# IV_Swinger_2_cell.net
KiCad netlist of a schematic drawn in EAGLE
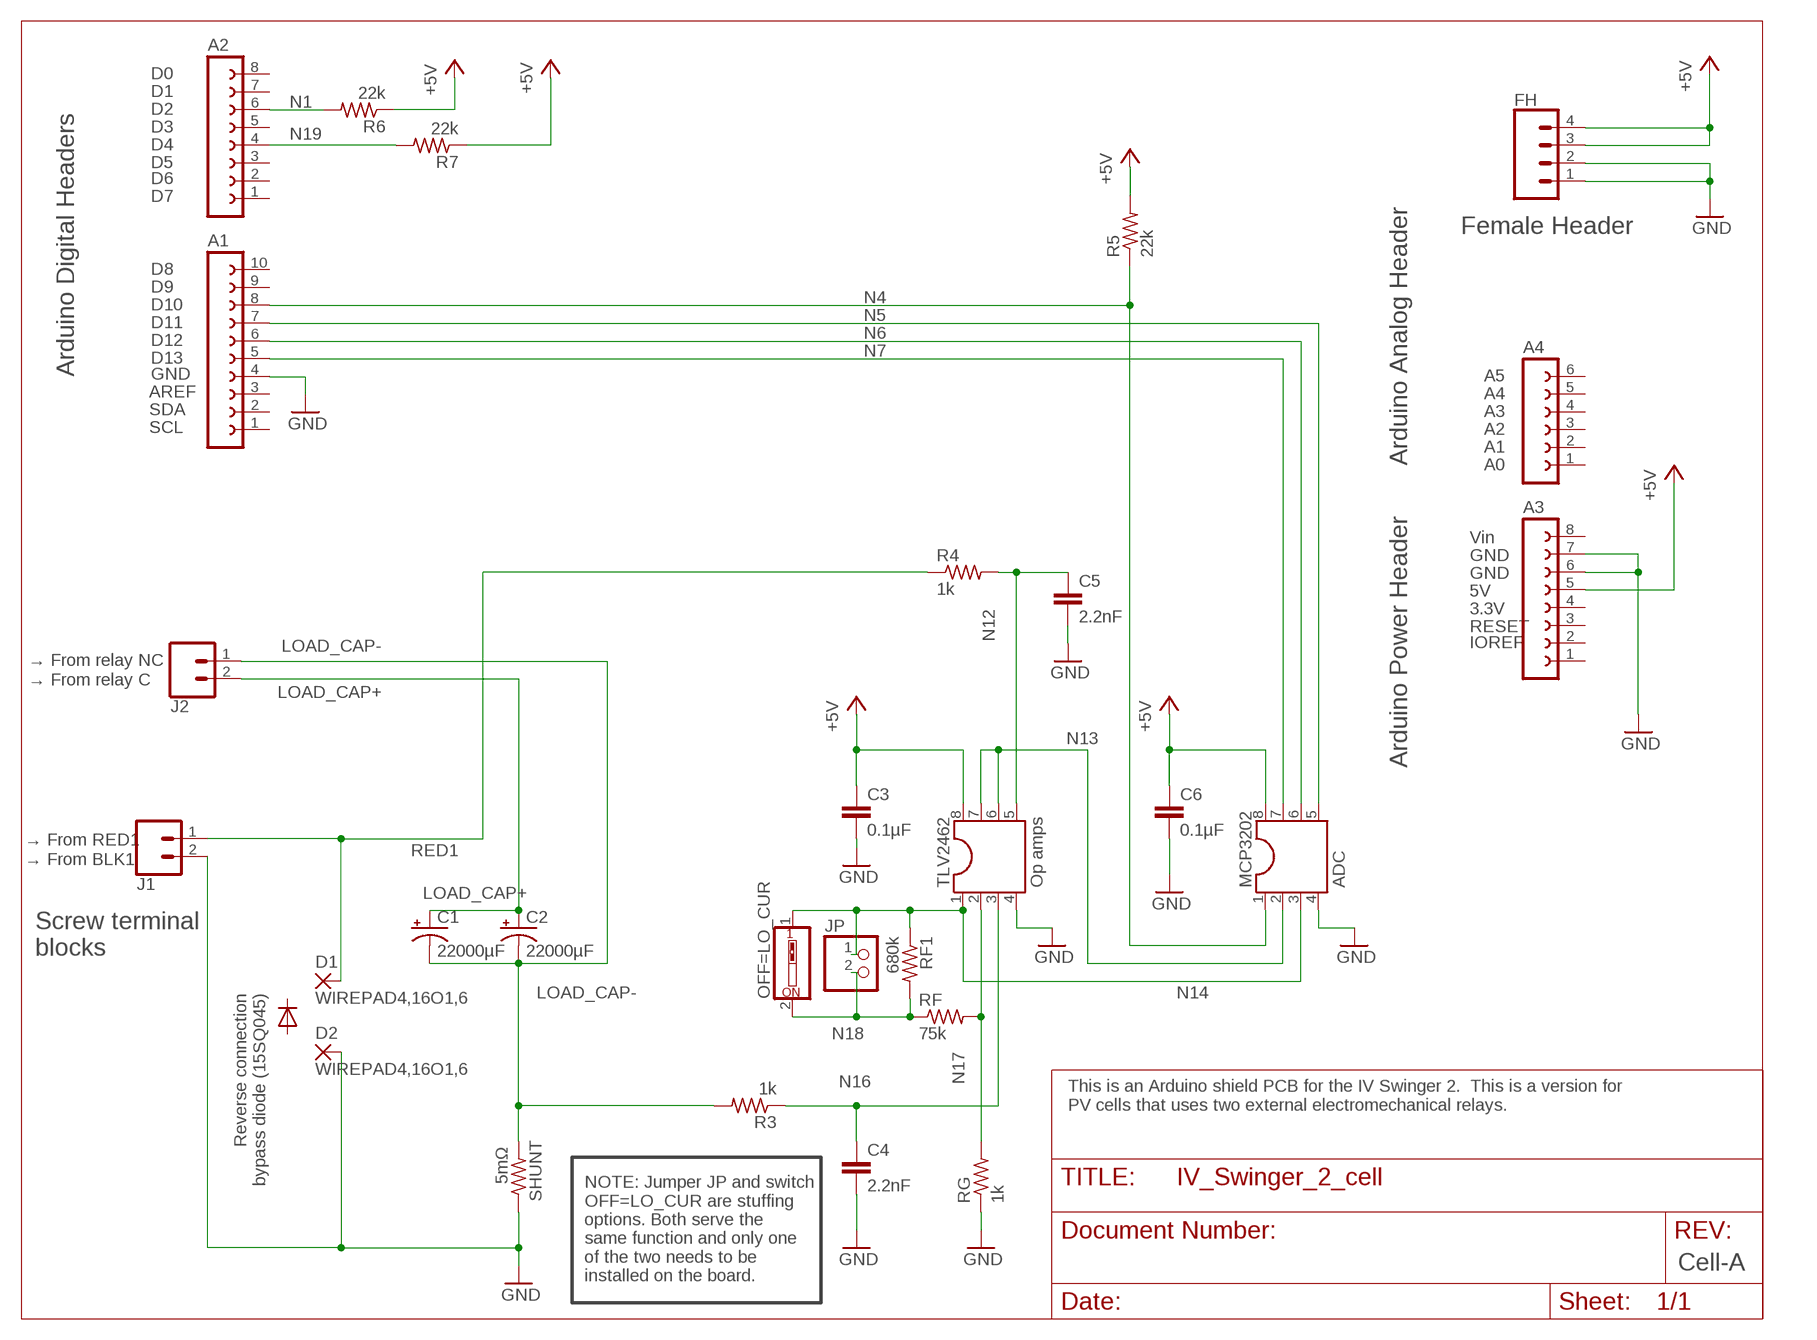
[diagram p0: schematic, sheet 1]

(export (version "E")
  (design (tool "Eeschema 10.0.6"))
  (components
    (comp (ref "A1")
      (value "FE10-1")
      (footprint "eagle-import:FE10")
      (libsource (lib "eagle-import") (part "FE10-1"))
    )
    (comp (ref "A2")
      (value "FE08-1")
      (footprint "eagle-import:FE08")
      (libsource (lib "eagle-import") (part "FE08-1"))
    )
    (comp (ref "A3")
      (value "FE08-1")
      (footprint "eagle-import:FE08")
      (libsource (lib "eagle-import") (part "FE08-1"))
    )
    (comp (ref "A4")
      (value "FE06-1")
      (footprint "eagle-import:FE06")
      (libsource (lib "eagle-import") (part "FE06-1"))
    )
    (comp (ref "C1")
      (value "22000µF")
      (footprint "eagle-import:E7,5-18")
      (libsource (lib "eagle-import") (part "CPOL-USE7.5-18"))
    )
    (comp (ref "C2")
      (value "22000µF")
      (footprint "eagle-import:E7,5-18")
      (libsource (lib "eagle-import") (part "CPOL-USE7.5-18"))
    )
    (comp (ref "C3")
      (value "0.1µF")
      (footprint "eagle-import:C025-030X050")
      (libsource (lib "eagle-import") (part "C-EU025-030X050"))
    )
    (comp (ref "C4")
      (value "2.2nF")
      (footprint "eagle-import:C025-030X050")
      (libsource (lib "eagle-import") (part "C-EU025-030X050"))
    )
    (comp (ref "C5")
      (value "2.2nF")
      (footprint "eagle-import:C025-030X050")
      (libsource (lib "eagle-import") (part "C-EU025-030X050"))
    )
    (comp (ref "C6")
      (value "0.1µF")
      (footprint "eagle-import:C025-030X050")
      (libsource (lib "eagle-import") (part "C-EU025-030X050"))
    )
    (comp (ref "D1")
      (value "WIREPAD4,16O1,6")
      (footprint "eagle-import:4,16O1,6")
      (fields (field (name "SPICEPREFIX") "X"))
      (libsource (lib "eagle-import") (part "WIREPAD4,16O1,6"))
    )
    (comp (ref "D2")
      (value "WIREPAD4,16O1,6")
      (footprint "eagle-import:4,16O1,6")
      (libsource (lib "eagle-import") (part "WIREPAD4,16O1,6"))
    )
    (comp (ref "FH")
      (value "CONN_04LONGPADS")
      (footprint "eagle-import:1X04_LONGPADS")
      (libsource (lib "eagle-import") (part "CONN_04LONGPADS"))
    )
    (comp (ref "J1")
      (value "CONN_025MM")
      (footprint "eagle-import:SCREWTERMINAL-5MM-2")
      (libsource (lib "eagle-import") (part "CONN_025MM"))
    )
    (comp (ref "J2")
      (value "CONN_025MM")
      (footprint "eagle-import:SCREWTERMINAL-5MM-2")
      (libsource (lib "eagle-import") (part "CONN_025MM"))
    )
    (comp (ref "JP")
      (value "PINHD-1X2")
      (footprint "eagle-import:1X02")
      (libsource (lib "eagle-import") (part "PINHD-1X2"))
    )
    (comp (ref "MCP3202")
      (value "ADC")
      (footprint "eagle-import:SOCKET-08")
      (libsource (lib "eagle-import") (part "DIL8S"))
    )
    (comp (ref "OFF=LO_CUR")
      (value "SW_DIP-1")
      (footprint "eagle-import:EDG-01")
      (libsource (lib "eagle-import") (part "SW_DIP-1"))
    )
    (comp (ref "R3")
      (value "1k")
      (footprint "eagle-import:0207_10")
      (libsource (lib "eagle-import") (part "R-US_0207/10"))
    )
    (comp (ref "R4")
      (value "1k")
      (footprint "eagle-import:0207_10")
      (libsource (lib "eagle-import") (part "R-US_0207/10"))
    )
    (comp (ref "R5")
      (value "22k")
      (footprint "eagle-import:0207_10")
      (libsource (lib "eagle-import") (part "R-US_0207/10"))
    )
    (comp (ref "R6")
      (value "22k")
      (footprint "eagle-import:0207_10")
      (libsource (lib "eagle-import") (part "R-US_0207/10"))
    )
    (comp (ref "R7")
      (value "22k")
      (footprint "eagle-import:0207_10")
      (libsource (lib "eagle-import") (part "R-US_0207/10"))
    )
    (comp (ref "RF")
      (value "75k")
      (footprint "eagle-import:0207_10")
      (libsource (lib "eagle-import") (part "R-US_0207/10"))
    )
    (comp (ref "RF1")
      (value "680k")
      (footprint "eagle-import:0207_10")
      (libsource (lib "eagle-import") (part "R-US_0207/10"))
    )
    (comp (ref "RG")
      (value "1k")
      (footprint "eagle-import:0207_10")
      (libsource (lib "eagle-import") (part "R-US_0207/10"))
    )
    (comp (ref "SHUNT")
      (value "5mΩ")
      (footprint "eagle-import:0617_17")
      (libsource (lib "eagle-import") (part "R-US_0617/17"))
    )
    (comp (ref "TLV2462")
      (value "Op amps")
      (footprint "eagle-import:SOCKET-08")
      (libsource (lib "eagle-import") (part "DIL8S"))
    )
  )
  (nets
    (net (code "1") (name "+5V") (class "Default")
      (node (ref "A3") (pin "5") (pinfunction "5_5") (pintype "passive"))
      (node (ref "C3") (pin "1") (pinfunction "1_1") (pintype "passive"))
      (node (ref "C6") (pin "1") (pinfunction "1_1") (pintype "passive"))
      (node (ref "FH") (pin "3") (pinfunction "3_3") (pintype "passive"))
      (node (ref "FH") (pin "4") (pinfunction "4_4") (pintype "passive"))
      (node (ref "MCP3202") (pin "8") (pinfunction "8_8") (pintype "passive"))
      (node (ref "R5") (pin "2") (pinfunction "2_2") (pintype "passive"))
      (node (ref "R6") (pin "1") (pinfunction "1_1") (pintype "passive"))
      (node (ref "R7") (pin "1") (pinfunction "1_1") (pintype "passive"))
      (node (ref "TLV2462") (pin "8") (pinfunction "8_8") (pintype "passive"))
    )
    (net (code "2") (name "/LOAD_CAP+") (class "Default")
      (node (ref "C1") (pin "+") (pinfunction "+_+") (pintype "passive"))
      (node (ref "C2") (pin "+") (pinfunction "+_+") (pintype "passive"))
      (node (ref "J2") (pin "2") (pinfunction "2_2") (pintype "passive"))
    )
    (net (code "3") (name "/LOAD_CAP-") (class "Default")
      (node (ref "C1") (pin "-") (pinfunction "-_-") (pintype "passive"))
      (node (ref "C2") (pin "-") (pinfunction "-_-") (pintype "passive"))
      (node (ref "J2") (pin "1") (pinfunction "1_1") (pintype "passive"))
      (node (ref "R3") (pin "2") (pinfunction "2_2") (pintype "passive"))
      (node (ref "SHUNT") (pin "2") (pinfunction "2_2") (pintype "passive"))
    )
    (net (code "4") (name "/N1") (class "Default")
      (node (ref "A2") (pin "6") (pinfunction "6_6") (pintype "passive"))
      (node (ref "R6") (pin "2") (pinfunction "2_2") (pintype "passive"))
    )
    (net (code "5") (name "/N4") (class "Default")
      (node (ref "A1") (pin "8") (pinfunction "8_8") (pintype "passive"))
      (node (ref "MCP3202") (pin "1") (pinfunction "1_1") (pintype "passive"))
      (node (ref "R5") (pin "1") (pinfunction "1_1") (pintype "passive"))
    )
    (net (code "6") (name "/N5") (class "Default")
      (node (ref "A1") (pin "7") (pinfunction "7_7") (pintype "passive"))
      (node (ref "MCP3202") (pin "5") (pinfunction "5_5") (pintype "passive"))
    )
    (net (code "7") (name "/N6") (class "Default")
      (node (ref "A1") (pin "6") (pinfunction "6_6") (pintype "passive"))
      (node (ref "MCP3202") (pin "6") (pinfunction "6_6") (pintype "passive"))
    )
    (net (code "8") (name "/N7") (class "Default")
      (node (ref "A1") (pin "5") (pinfunction "5_5") (pintype "passive"))
      (node (ref "MCP3202") (pin "7") (pinfunction "7_7") (pintype "passive"))
    )
    (net (code "9") (name "/N12") (class "Default")
      (node (ref "C5") (pin "1") (pinfunction "1_1") (pintype "passive"))
      (node (ref "R4") (pin "2") (pinfunction "2_2") (pintype "passive"))
      (node (ref "TLV2462") (pin "5") (pinfunction "5_5") (pintype "passive"))
    )
    (net (code "10") (name "/N13") (class "Default")
      (node (ref "MCP3202") (pin "2") (pinfunction "2_2") (pintype "passive"))
      (node (ref "TLV2462") (pin "6") (pinfunction "6_6") (pintype "passive"))
      (node (ref "TLV2462") (pin "7") (pinfunction "7_7") (pintype "passive"))
    )
    (net (code "11") (name "/N14") (class "Default")
      (node (ref "JP") (pin "1") (pinfunction "1_1") (pintype "passive"))
      (node (ref "MCP3202") (pin "3") (pinfunction "3_3") (pintype "passive"))
      (node (ref "OFF=LO_CUR") (pin "1") (pinfunction "1_1") (pintype "passive"))
      (node (ref "RF1") (pin "1") (pinfunction "1_1") (pintype "passive"))
      (node (ref "TLV2462") (pin "1") (pinfunction "1_1") (pintype "passive"))
    )
    (net (code "12") (name "/N16") (class "Default")
      (node (ref "C4") (pin "1") (pinfunction "1_1") (pintype "passive"))
      (node (ref "R3") (pin "1") (pinfunction "1_1") (pintype "passive"))
      (node (ref "TLV2462") (pin "3") (pinfunction "3_3") (pintype "passive"))
    )
    (net (code "13") (name "/N17") (class "Default")
      (node (ref "RF") (pin "2") (pinfunction "2_2") (pintype "passive"))
      (node (ref "RG") (pin "2") (pinfunction "2_2") (pintype "passive"))
      (node (ref "TLV2462") (pin "2") (pinfunction "2_2") (pintype "passive"))
    )
    (net (code "14") (name "/N18") (class "Default")
      (node (ref "JP") (pin "2") (pinfunction "2_2") (pintype "passive"))
      (node (ref "OFF=LO_CUR") (pin "2") (pinfunction "2_2") (pintype "passive"))
      (node (ref "RF") (pin "1") (pinfunction "1_1") (pintype "passive"))
      (node (ref "RF1") (pin "2") (pinfunction "2_2") (pintype "passive"))
    )
    (net (code "15") (name "/N19") (class "Default")
      (node (ref "A2") (pin "4") (pinfunction "4_4") (pintype "passive"))
      (node (ref "R7") (pin "2") (pinfunction "2_2") (pintype "passive"))
    )
    (net (code "16") (name "/RED1") (class "Default")
      (node (ref "D1") (pin "1") (pinfunction "P_1") (pintype "passive"))
      (node (ref "J1") (pin "1") (pinfunction "1_1") (pintype "passive"))
      (node (ref "R4") (pin "1") (pinfunction "1_1") (pintype "passive"))
    )
    (net (code "17") (name "GND") (class "Default")
      (node (ref "A1") (pin "4") (pinfunction "4_4") (pintype "passive"))
      (node (ref "A3") (pin "6") (pinfunction "6_6") (pintype "passive"))
      (node (ref "A3") (pin "7") (pinfunction "7_7") (pintype "passive"))
      (node (ref "C3") (pin "2") (pinfunction "2_2") (pintype "passive"))
      (node (ref "C4") (pin "2") (pinfunction "2_2") (pintype "passive"))
      (node (ref "C5") (pin "2") (pinfunction "2_2") (pintype "passive"))
      (node (ref "C6") (pin "2") (pinfunction "2_2") (pintype "passive"))
      (node (ref "D2") (pin "1") (pinfunction "P_1") (pintype "passive"))
      (node (ref "FH") (pin "1") (pinfunction "1_1") (pintype "passive"))
      (node (ref "FH") (pin "2") (pinfunction "2_2") (pintype "passive"))
      (node (ref "J1") (pin "2") (pinfunction "2_2") (pintype "passive"))
      (node (ref "MCP3202") (pin "4") (pinfunction "4_4") (pintype "passive"))
      (node (ref "RG") (pin "1") (pinfunction "1_1") (pintype "passive"))
      (node (ref "SHUNT") (pin "1") (pinfunction "1_1") (pintype "passive"))
      (node (ref "TLV2462") (pin "4") (pinfunction "4_4") (pintype "passive"))
    )
    (net (code "18") (name "unconnected-(A1-Pad1)") (class "Default")
      (node (ref "A1") (pin "1") (pinfunction "1_1") (pintype "passive"))
    )
    (net (code "19") (name "unconnected-(A1-Pad2)") (class "Default")
      (node (ref "A1") (pin "2") (pinfunction "2_2") (pintype "passive"))
    )
    (net (code "20") (name "unconnected-(A1-Pad3)") (class "Default")
      (node (ref "A1") (pin "3") (pinfunction "3_3") (pintype "passive"))
    )
    (net (code "21") (name "unconnected-(A1-Pad9)") (class "Default")
      (node (ref "A1") (pin "9") (pinfunction "9_9") (pintype "passive"))
    )
    (net (code "22") (name "unconnected-(A1-Pad10)") (class "Default")
      (node (ref "A1") (pin "10") (pinfunction "10_10") (pintype "passive"))
    )
    (net (code "23") (name "unconnected-(A2-Pad1)") (class "Default")
      (node (ref "A2") (pin "1") (pinfunction "1_1") (pintype "passive"))
    )
    (net (code "24") (name "unconnected-(A2-Pad2)") (class "Default")
      (node (ref "A2") (pin "2") (pinfunction "2_2") (pintype "passive"))
    )
    (net (code "25") (name "unconnected-(A2-Pad3)") (class "Default")
      (node (ref "A2") (pin "3") (pinfunction "3_3") (pintype "passive"))
    )
    (net (code "26") (name "unconnected-(A2-Pad5)") (class "Default")
      (node (ref "A2") (pin "5") (pinfunction "5_5") (pintype "passive"))
    )
    (net (code "27") (name "unconnected-(A2-Pad7)") (class "Default")
      (node (ref "A2") (pin "7") (pinfunction "7_7") (pintype "passive"))
    )
    (net (code "28") (name "unconnected-(A2-Pad8)") (class "Default")
      (node (ref "A2") (pin "8") (pinfunction "8_8") (pintype "passive"))
    )
    (net (code "29") (name "unconnected-(A3-Pad1)") (class "Default")
      (node (ref "A3") (pin "1") (pinfunction "1_1") (pintype "passive"))
    )
    (net (code "30") (name "unconnected-(A3-Pad2)") (class "Default")
      (node (ref "A3") (pin "2") (pinfunction "2_2") (pintype "passive"))
    )
    (net (code "31") (name "unconnected-(A3-Pad3)") (class "Default")
      (node (ref "A3") (pin "3") (pinfunction "3_3") (pintype "passive"))
    )
    (net (code "32") (name "unconnected-(A3-Pad4)") (class "Default")
      (node (ref "A3") (pin "4") (pinfunction "4_4") (pintype "passive"))
    )
    (net (code "33") (name "unconnected-(A3-Pad8)") (class "Default")
      (node (ref "A3") (pin "8") (pinfunction "8_8") (pintype "passive"))
    )
    (net (code "34") (name "unconnected-(A4-Pad1)") (class "Default")
      (node (ref "A4") (pin "1") (pinfunction "1_1") (pintype "passive"))
    )
    (net (code "35") (name "unconnected-(A4-Pad2)") (class "Default")
      (node (ref "A4") (pin "2") (pinfunction "2_2") (pintype "passive"))
    )
    (net (code "36") (name "unconnected-(A4-Pad3)") (class "Default")
      (node (ref "A4") (pin "3") (pinfunction "3_3") (pintype "passive"))
    )
    (net (code "37") (name "unconnected-(A4-Pad4)") (class "Default")
      (node (ref "A4") (pin "4") (pinfunction "4_4") (pintype "passive"))
    )
    (net (code "38") (name "unconnected-(A4-Pad5)") (class "Default")
      (node (ref "A4") (pin "5") (pinfunction "5_5") (pintype "passive"))
    )
    (net (code "39") (name "unconnected-(A4-Pad6)") (class "Default")
      (node (ref "A4") (pin "6") (pinfunction "6_6") (pintype "passive"))
    )
  )
)
